# rfLED2.net
KiCad netlist of a schematic drawn in EAGLE
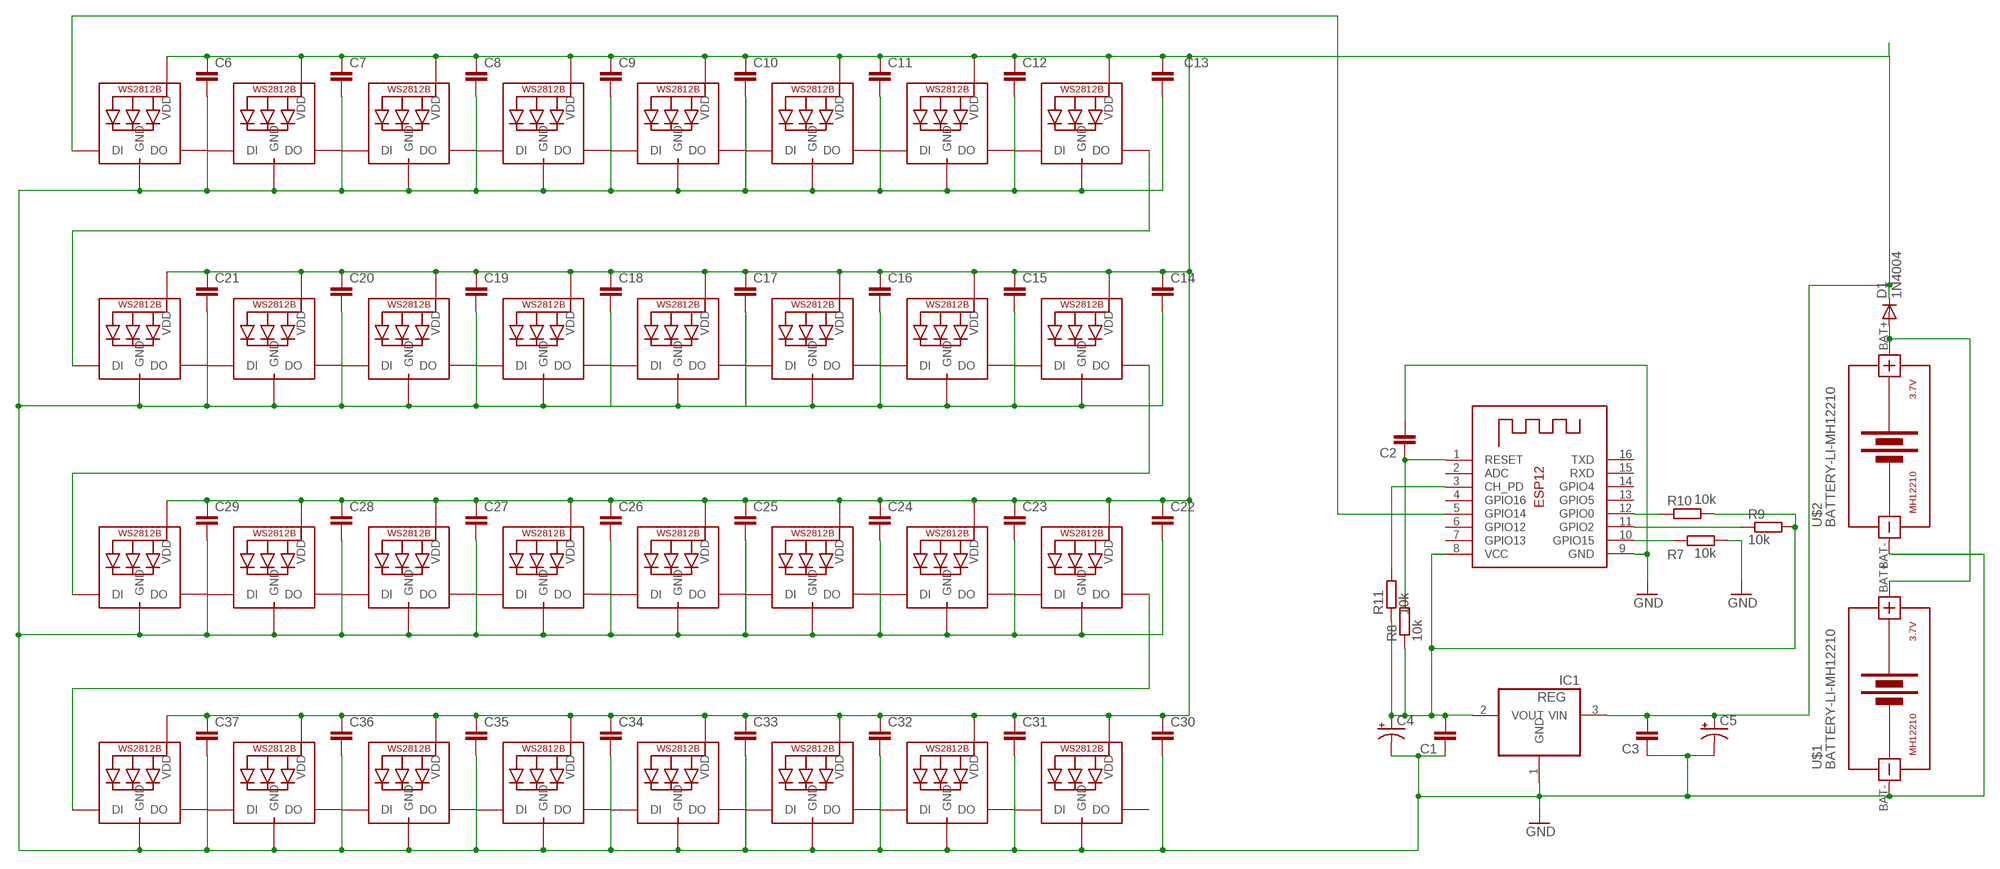
[diagram p0: schematic, sheet 1]

(export (version "E")
  (design (tool "Eeschema 10.0.6"))
  (components
    (comp (ref "C1") (value "C") (footprint "eagle-import:C0805") (libsource (lib "eagle-import") (part "C")))
    (comp (ref "C2") (value "C") (footprint "eagle-import:C0805") (libsource (lib "eagle-import") (part "C")))
    (comp (ref "C3") (value "C") (footprint "eagle-import:C0805") (libsource (lib "eagle-import") (part "C")))
    (comp (ref "C4")
      (value "CPOL-US150CLZ-1010")
      (footprint "eagle-import:150CLZ-1010")
      (libsource (lib "eagle-import") (part "CPOL-US150CLZ-1010"))
    )
    (comp (ref "C5")
      (value "CPOL-US150CLZ-1010")
      (footprint "eagle-import:150CLZ-1010")
      (libsource (lib "eagle-import") (part "CPOL-US150CLZ-1010"))
    )
    (comp (ref "C6") (value "C") (footprint "eagle-import:C0805") (libsource (lib "eagle-import") (part "C")))
    (comp (ref "C7") (value "C") (footprint "eagle-import:C0805") (libsource (lib "eagle-import") (part "C")))
    (comp (ref "C8") (value "C") (footprint "eagle-import:C0805") (libsource (lib "eagle-import") (part "C")))
    (comp (ref "C9") (value "C") (footprint "eagle-import:C0805") (libsource (lib "eagle-import") (part "C")))
    (comp (ref "C10")
      (value "C")
      (footprint "eagle-import:C0805")
      (libsource (lib "eagle-import") (part "C"))
    )
    (comp (ref "C11")
      (value "C")
      (footprint "eagle-import:C0805")
      (libsource (lib "eagle-import") (part "C"))
    )
    (comp (ref "C12")
      (value "C")
      (footprint "eagle-import:C0805")
      (libsource (lib "eagle-import") (part "C"))
    )
    (comp (ref "C13")
      (value "C")
      (footprint "eagle-import:C0805")
      (libsource (lib "eagle-import") (part "C"))
    )
    (comp (ref "C14")
      (value "C")
      (footprint "eagle-import:C0805")
      (libsource (lib "eagle-import") (part "C"))
    )
    (comp (ref "C15")
      (value "C")
      (footprint "eagle-import:C0805")
      (libsource (lib "eagle-import") (part "C"))
    )
    (comp (ref "C16")
      (value "C")
      (footprint "eagle-import:C0805")
      (libsource (lib "eagle-import") (part "C"))
    )
    (comp (ref "C17")
      (value "C")
      (footprint "eagle-import:C0805")
      (libsource (lib "eagle-import") (part "C"))
    )
    (comp (ref "C18")
      (value "C")
      (footprint "eagle-import:C0805")
      (libsource (lib "eagle-import") (part "C"))
    )
    (comp (ref "C19")
      (value "C")
      (footprint "eagle-import:C0805")
      (libsource (lib "eagle-import") (part "C"))
    )
    (comp (ref "C20")
      (value "C")
      (footprint "eagle-import:C0805")
      (libsource (lib "eagle-import") (part "C"))
    )
    (comp (ref "C21")
      (value "C")
      (footprint "eagle-import:C0805")
      (libsource (lib "eagle-import") (part "C"))
    )
    (comp (ref "C22")
      (value "C")
      (footprint "eagle-import:C0805")
      (libsource (lib "eagle-import") (part "C"))
    )
    (comp (ref "C23")
      (value "C")
      (footprint "eagle-import:C0805")
      (libsource (lib "eagle-import") (part "C"))
    )
    (comp (ref "C24")
      (value "C")
      (footprint "eagle-import:C0805")
      (libsource (lib "eagle-import") (part "C"))
    )
    (comp (ref "C25")
      (value "C")
      (footprint "eagle-import:C0805")
      (libsource (lib "eagle-import") (part "C"))
    )
    (comp (ref "C26")
      (value "C")
      (footprint "eagle-import:C0805")
      (libsource (lib "eagle-import") (part "C"))
    )
    (comp (ref "C27")
      (value "C")
      (footprint "eagle-import:C0805")
      (libsource (lib "eagle-import") (part "C"))
    )
    (comp (ref "C28")
      (value "C")
      (footprint "eagle-import:C0805")
      (libsource (lib "eagle-import") (part "C"))
    )
    (comp (ref "C29")
      (value "C")
      (footprint "eagle-import:C0805")
      (libsource (lib "eagle-import") (part "C"))
    )
    (comp (ref "C30")
      (value "C")
      (footprint "eagle-import:C0805")
      (libsource (lib "eagle-import") (part "C"))
    )
    (comp (ref "C31")
      (value "C")
      (footprint "eagle-import:C0805")
      (libsource (lib "eagle-import") (part "C"))
    )
    (comp (ref "C32")
      (value "C")
      (footprint "eagle-import:C0805")
      (libsource (lib "eagle-import") (part "C"))
    )
    (comp (ref "C33")
      (value "C")
      (footprint "eagle-import:C0805")
      (libsource (lib "eagle-import") (part "C"))
    )
    (comp (ref "C34")
      (value "C")
      (footprint "eagle-import:C0805")
      (libsource (lib "eagle-import") (part "C"))
    )
    (comp (ref "C35")
      (value "C")
      (footprint "eagle-import:C0805")
      (libsource (lib "eagle-import") (part "C"))
    )
    (comp (ref "C36")
      (value "C")
      (footprint "eagle-import:C0805")
      (libsource (lib "eagle-import") (part "C"))
    )
    (comp (ref "C37")
      (value "C")
      (footprint "eagle-import:C0805")
      (libsource (lib "eagle-import") (part "C"))
    )
    (comp (ref "D1")
      (value "1N4004")
      (footprint "eagle-import:DO41-10")
      (libsource (lib "eagle-import") (part "1N4004"))
    )
    (comp (ref "IC1")
      (value "REG")
      (footprint "eagle-import:SOT223")
      (fields (field (name "MPN") "REG1117"))
      (libsource (lib "eagle-import") (part "REG1117"))
    )
    (comp (ref "LED1")
      (value "WS2812B5050")
      (footprint "eagle-import:WS2812B")
      (libsource (lib "eagle-import") (part "WS2812B5050"))
    )
    (comp (ref "LED2")
      (value "WS2812B5050")
      (footprint "eagle-import:WS2812B")
      (libsource (lib "eagle-import") (part "WS2812B5050"))
    )
    (comp (ref "LED3")
      (value "WS2812B5050")
      (footprint "eagle-import:WS2812B")
      (libsource (lib "eagle-import") (part "WS2812B5050"))
    )
    (comp (ref "LED4")
      (value "WS2812B5050")
      (footprint "eagle-import:WS2812B")
      (libsource (lib "eagle-import") (part "WS2812B5050"))
    )
    (comp (ref "LED5")
      (value "WS2812B5050")
      (footprint "eagle-import:WS2812B")
      (libsource (lib "eagle-import") (part "WS2812B5050"))
    )
    (comp (ref "LED6")
      (value "WS2812B5050")
      (footprint "eagle-import:WS2812B")
      (libsource (lib "eagle-import") (part "WS2812B5050"))
    )
    (comp (ref "LED7")
      (value "WS2812B5050")
      (footprint "eagle-import:WS2812B")
      (libsource (lib "eagle-import") (part "WS2812B5050"))
    )
    (comp (ref "LED8")
      (value "WS2812B5050")
      (footprint "eagle-import:WS2812B")
      (libsource (lib "eagle-import") (part "WS2812B5050"))
    )
    (comp (ref "LED9")
      (value "WS2812B5050")
      (footprint "eagle-import:WS2812B")
      (libsource (lib "eagle-import") (part "WS2812B5050"))
    )
    (comp (ref "LED10")
      (value "WS2812B5050")
      (footprint "eagle-import:WS2812B")
      (libsource (lib "eagle-import") (part "WS2812B5050"))
    )
    (comp (ref "LED11")
      (value "WS2812B5050")
      (footprint "eagle-import:WS2812B")
      (libsource (lib "eagle-import") (part "WS2812B5050"))
    )
    (comp (ref "LED12")
      (value "WS2812B5050")
      (footprint "eagle-import:WS2812B")
      (libsource (lib "eagle-import") (part "WS2812B5050"))
    )
    (comp (ref "LED13")
      (value "WS2812B5050")
      (footprint "eagle-import:WS2812B")
      (libsource (lib "eagle-import") (part "WS2812B5050"))
    )
    (comp (ref "LED14")
      (value "WS2812B5050")
      (footprint "eagle-import:WS2812B")
      (libsource (lib "eagle-import") (part "WS2812B5050"))
    )
    (comp (ref "LED15")
      (value "WS2812B5050")
      (footprint "eagle-import:WS2812B")
      (libsource (lib "eagle-import") (part "WS2812B5050"))
    )
    (comp (ref "LED16")
      (value "WS2812B5050")
      (footprint "eagle-import:WS2812B")
      (libsource (lib "eagle-import") (part "WS2812B5050"))
    )
    (comp (ref "LED17")
      (value "WS2812B5050")
      (footprint "eagle-import:WS2812B")
      (libsource (lib "eagle-import") (part "WS2812B5050"))
    )
    (comp (ref "LED18")
      (value "WS2812B5050")
      (footprint "eagle-import:WS2812B")
      (libsource (lib "eagle-import") (part "WS2812B5050"))
    )
    (comp (ref "LED19")
      (value "WS2812B5050")
      (footprint "eagle-import:WS2812B")
      (libsource (lib "eagle-import") (part "WS2812B5050"))
    )
    (comp (ref "LED20")
      (value "WS2812B5050")
      (footprint "eagle-import:WS2812B")
      (libsource (lib "eagle-import") (part "WS2812B5050"))
    )
    (comp (ref "LED21")
      (value "WS2812B5050")
      (footprint "eagle-import:WS2812B")
      (libsource (lib "eagle-import") (part "WS2812B5050"))
    )
    (comp (ref "LED22")
      (value "WS2812B5050")
      (footprint "eagle-import:WS2812B")
      (libsource (lib "eagle-import") (part "WS2812B5050"))
    )
    (comp (ref "LED23")
      (value "WS2812B5050")
      (footprint "eagle-import:WS2812B")
      (libsource (lib "eagle-import") (part "WS2812B5050"))
    )
    (comp (ref "LED24")
      (value "WS2812B5050")
      (footprint "eagle-import:WS2812B")
      (libsource (lib "eagle-import") (part "WS2812B5050"))
    )
    (comp (ref "LED25")
      (value "WS2812B5050")
      (footprint "eagle-import:WS2812B")
      (libsource (lib "eagle-import") (part "WS2812B5050"))
    )
    (comp (ref "LED26")
      (value "WS2812B5050")
      (footprint "eagle-import:WS2812B")
      (libsource (lib "eagle-import") (part "WS2812B5050"))
    )
    (comp (ref "LED27")
      (value "WS2812B5050")
      (footprint "eagle-import:WS2812B")
      (libsource (lib "eagle-import") (part "WS2812B5050"))
    )
    (comp (ref "LED28")
      (value "WS2812B5050")
      (footprint "eagle-import:WS2812B")
      (libsource (lib "eagle-import") (part "WS2812B5050"))
    )
    (comp (ref "LED29")
      (value "WS2812B5050")
      (footprint "eagle-import:WS2812B")
      (libsource (lib "eagle-import") (part "WS2812B5050"))
    )
    (comp (ref "LED30")
      (value "WS2812B5050")
      (footprint "eagle-import:WS2812B")
      (libsource (lib "eagle-import") (part "WS2812B5050"))
    )
    (comp (ref "LED31")
      (value "WS2812B5050")
      (footprint "eagle-import:WS2812B")
      (libsource (lib "eagle-import") (part "WS2812B5050"))
    )
    (comp (ref "LED32")
      (value "WS2812B5050")
      (footprint "eagle-import:WS2812B")
      (libsource (lib "eagle-import") (part "WS2812B5050"))
    )
    (comp (ref "R7")
      (value "10k")
      (footprint "eagle-import:R1206")
      (libsource (lib "eagle-import") (part "RR1206"))
    )
    (comp (ref "R8")
      (value "10k")
      (footprint "eagle-import:R1206")
      (libsource (lib "eagle-import") (part "RR1206"))
    )
    (comp (ref "R9")
      (value "10k")
      (footprint "eagle-import:R1206")
      (libsource (lib "eagle-import") (part "RR1206"))
    )
    (comp (ref "R10")
      (value "10k")
      (footprint "eagle-import:R1206")
      (libsource (lib "eagle-import") (part "RR1206"))
    )
    (comp (ref "R11")
      (value "10k")
      (footprint "eagle-import:R1206")
      (libsource (lib "eagle-import") (part "RR1206"))
    )
    (comp (ref "U$1")
      (value "BATTERY-LI-MH12210")
      (footprint "eagle-import:BATTERY-LI-MH12210")
      (libsource (lib "eagle-import") (part "BATTERY-LI-MH12210"))
    )
    (comp (ref "U$2")
      (value "BATTERY-LI-MH12210")
      (footprint "eagle-import:BATTERY-LI-MH12210")
      (libsource (lib "eagle-import") (part "BATTERY-LI-MH12210"))
    )
    (comp (ref "X1")
      (value "ESP-12")
      (footprint "eagle-import:ESP-12")
      (libsource (lib "eagle-import") (part "ESP-12"))
    )
  )
  (nets
    (net (code "1") (name "GND") (class "Default")
      (node (ref "C1") (pin "1") (pinfunction "1_1") (pintype "passive"))
      (node (ref "C10") (pin "2") (pinfunction "2_2") (pintype "passive"))
      (node (ref "C11") (pin "2") (pinfunction "2_2") (pintype "passive"))
      (node (ref "C12") (pin "2") (pinfunction "2_2") (pintype "passive"))
      (node (ref "C13") (pin "2") (pinfunction "2_2") (pintype "passive"))
      (node (ref "C14") (pin "2") (pinfunction "2_2") (pintype "passive"))
      (node (ref "C15") (pin "2") (pinfunction "2_2") (pintype "passive"))
      (node (ref "C16") (pin "2") (pinfunction "2_2") (pintype "passive"))
      (node (ref "C17") (pin "2") (pinfunction "2_2") (pintype "passive"))
      (node (ref "C18") (pin "2") (pinfunction "2_2") (pintype "passive"))
      (node (ref "C19") (pin "2") (pinfunction "2_2") (pintype "passive"))
      (node (ref "C2") (pin "2") (pinfunction "2_2") (pintype "passive"))
      (node (ref "C20") (pin "2") (pinfunction "2_2") (pintype "passive"))
      (node (ref "C21") (pin "2") (pinfunction "2_2") (pintype "passive"))
      (node (ref "C22") (pin "2") (pinfunction "2_2") (pintype "passive"))
      (node (ref "C23") (pin "2") (pinfunction "2_2") (pintype "passive"))
      (node (ref "C24") (pin "2") (pinfunction "2_2") (pintype "passive"))
      (node (ref "C25") (pin "2") (pinfunction "2_2") (pintype "passive"))
      (node (ref "C26") (pin "2") (pinfunction "2_2") (pintype "passive"))
      (node (ref "C27") (pin "2") (pinfunction "2_2") (pintype "passive"))
      (node (ref "C28") (pin "2") (pinfunction "2_2") (pintype "passive"))
      (node (ref "C29") (pin "2") (pinfunction "2_2") (pintype "passive"))
      (node (ref "C3") (pin "1") (pinfunction "1_1") (pintype "passive"))
      (node (ref "C30") (pin "2") (pinfunction "2_2") (pintype "passive"))
      (node (ref "C31") (pin "2") (pinfunction "2_2") (pintype "passive"))
      (node (ref "C32") (pin "2") (pinfunction "2_2") (pintype "passive"))
      (node (ref "C33") (pin "2") (pinfunction "2_2") (pintype "passive"))
      (node (ref "C34") (pin "2") (pinfunction "2_2") (pintype "passive"))
      (node (ref "C35") (pin "2") (pinfunction "2_2") (pintype "passive"))
      (node (ref "C36") (pin "2") (pinfunction "2_2") (pintype "passive"))
      (node (ref "C37") (pin "2") (pinfunction "2_2") (pintype "passive"))
      (node (ref "C4") (pin "-") (pinfunction "-_-") (pintype "passive"))
      (node (ref "C5") (pin "-") (pinfunction "-_-") (pintype "passive"))
      (node (ref "C6") (pin "2") (pinfunction "2_2") (pintype "passive"))
      (node (ref "C7") (pin "2") (pinfunction "2_2") (pintype "passive"))
      (node (ref "C8") (pin "2") (pinfunction "2_2") (pintype "passive"))
      (node (ref "C9") (pin "2") (pinfunction "2_2") (pintype "passive"))
      (node (ref "IC1") (pin "1") (pinfunction "GND_1") (pintype "power_in"))
      (node (ref "LED1") (pin "3-GND") (pinfunction "GND_3-GND") (pintype "power_in"))
      (node (ref "LED10") (pin "3-GND") (pinfunction "GND_3-GND") (pintype "power_in"))
      (node (ref "LED11") (pin "3-GND") (pinfunction "GND_3-GND") (pintype "power_in"))
      (node (ref "LED12") (pin "3-GND") (pinfunction "GND_3-GND") (pintype "power_in"))
      (node (ref "LED13") (pin "3-GND") (pinfunction "GND_3-GND") (pintype "power_in"))
      (node (ref "LED14") (pin "3-GND") (pinfunction "GND_3-GND") (pintype "power_in"))
      (node (ref "LED15") (pin "3-GND") (pinfunction "GND_3-GND") (pintype "power_in"))
      (node (ref "LED16") (pin "3-GND") (pinfunction "GND_3-GND") (pintype "power_in"))
      (node (ref "LED17") (pin "3-GND") (pinfunction "GND_3-GND") (pintype "power_in"))
      (node (ref "LED18") (pin "3-GND") (pinfunction "GND_3-GND") (pintype "power_in"))
      (node (ref "LED19") (pin "3-GND") (pinfunction "GND_3-GND") (pintype "power_in"))
      (node (ref "LED2") (pin "3-GND") (pinfunction "GND_3-GND") (pintype "power_in"))
      (node (ref "LED20") (pin "3-GND") (pinfunction "GND_3-GND") (pintype "power_in"))
      (node (ref "LED21") (pin "3-GND") (pinfunction "GND_3-GND") (pintype "power_in"))
      (node (ref "LED22") (pin "3-GND") (pinfunction "GND_3-GND") (pintype "power_in"))
      (node (ref "LED23") (pin "3-GND") (pinfunction "GND_3-GND") (pintype "power_in"))
      (node (ref "LED24") (pin "3-GND") (pinfunction "GND_3-GND") (pintype "power_in"))
      (node (ref "LED25") (pin "3-GND") (pinfunction "GND_3-GND") (pintype "power_in"))
      (node (ref "LED26") (pin "3-GND") (pinfunction "GND_3-GND") (pintype "power_in"))
      (node (ref "LED27") (pin "3-GND") (pinfunction "GND_3-GND") (pintype "power_in"))
      (node (ref "LED28") (pin "3-GND") (pinfunction "GND_3-GND") (pintype "power_in"))
      (node (ref "LED29") (pin "3-GND") (pinfunction "GND_3-GND") (pintype "power_in"))
      (node (ref "LED3") (pin "3-GND") (pinfunction "GND_3-GND") (pintype "power_in"))
      (node (ref "LED30") (pin "3-GND") (pinfunction "GND_3-GND") (pintype "power_in"))
      (node (ref "LED31") (pin "3-GND") (pinfunction "GND_3-GND") (pintype "power_in"))
      (node (ref "LED32") (pin "3-GND") (pinfunction "GND_3-GND") (pintype "power_in"))
      (node (ref "LED4") (pin "3-GND") (pinfunction "GND_3-GND") (pintype "power_in"))
      (node (ref "LED5") (pin "3-GND") (pinfunction "GND_3-GND") (pintype "power_in"))
      (node (ref "LED6") (pin "3-GND") (pinfunction "GND_3-GND") (pintype "power_in"))
      (node (ref "LED7") (pin "3-GND") (pinfunction "GND_3-GND") (pintype "power_in"))
      (node (ref "LED8") (pin "3-GND") (pinfunction "GND_3-GND") (pintype "power_in"))
      (node (ref "LED9") (pin "3-GND") (pinfunction "GND_3-GND") (pintype "power_in"))
      (node (ref "R7") (pin "2") (pinfunction "2_2") (pintype "passive"))
      (node (ref "U$1") (pin "BAT-") (pinfunction "BAT-_BAT-") (pintype "power_in"))
      (node (ref "U$2") (pin "BAT-") (pinfunction "BAT-_BAT-") (pintype "power_in"))
      (node (ref "X1") (pin "9") (pinfunction "GND_9") (pintype "power_in"))
    )
    (net (code "2") (name "Net-(D1-PadA)") (class "Default")
      (node (ref "D1") (pin "A") (pinfunction "A_A") (pintype "passive"))
      (node (ref "U$1") (pin "BAT+") (pinfunction "BAT+_BAT+") (pintype "power_in"))
      (node (ref "U$2") (pin "BAT+") (pinfunction "BAT+_BAT+") (pintype "power_in"))
    )
    (net (code "3") (name "Net-(IC1-VIN)") (class "Default")
      (node (ref "C10") (pin "1") (pinfunction "1_1") (pintype "passive"))
      (node (ref "C11") (pin "1") (pinfunction "1_1") (pintype "passive"))
      (node (ref "C12") (pin "1") (pinfunction "1_1") (pintype "passive"))
      (node (ref "C13") (pin "1") (pinfunction "1_1") (pintype "passive"))
      (node (ref "C14") (pin "1") (pinfunction "1_1") (pintype "passive"))
      (node (ref "C15") (pin "1") (pinfunction "1_1") (pintype "passive"))
      (node (ref "C16") (pin "1") (pinfunction "1_1") (pintype "passive"))
      (node (ref "C17") (pin "1") (pinfunction "1_1") (pintype "passive"))
      (node (ref "C18") (pin "1") (pinfunction "1_1") (pintype "passive"))
      (node (ref "C19") (pin "1") (pinfunction "1_1") (pintype "passive"))
      (node (ref "C20") (pin "1") (pinfunction "1_1") (pintype "passive"))
      (node (ref "C21") (pin "1") (pinfunction "1_1") (pintype "passive"))
      (node (ref "C22") (pin "1") (pinfunction "1_1") (pintype "passive"))
      (node (ref "C23") (pin "1") (pinfunction "1_1") (pintype "passive"))
      (node (ref "C24") (pin "1") (pinfunction "1_1") (pintype "passive"))
      (node (ref "C25") (pin "1") (pinfunction "1_1") (pintype "passive"))
      (node (ref "C26") (pin "1") (pinfunction "1_1") (pintype "passive"))
      (node (ref "C27") (pin "1") (pinfunction "1_1") (pintype "passive"))
      (node (ref "C28") (pin "1") (pinfunction "1_1") (pintype "passive"))
      (node (ref "C29") (pin "1") (pinfunction "1_1") (pintype "passive"))
      (node (ref "C3") (pin "2") (pinfunction "2_2") (pintype "passive"))
      (node (ref "C30") (pin "1") (pinfunction "1_1") (pintype "passive"))
      (node (ref "C31") (pin "1") (pinfunction "1_1") (pintype "passive"))
      (node (ref "C32") (pin "1") (pinfunction "1_1") (pintype "passive"))
      (node (ref "C33") (pin "1") (pinfunction "1_1") (pintype "passive"))
      (node (ref "C34") (pin "1") (pinfunction "1_1") (pintype "passive"))
      (node (ref "C35") (pin "1") (pinfunction "1_1") (pintype "passive"))
      (node (ref "C36") (pin "1") (pinfunction "1_1") (pintype "passive"))
      (node (ref "C37") (pin "1") (pinfunction "1_1") (pintype "passive"))
      (node (ref "C5") (pin "+") (pinfunction "+_+") (pintype "passive"))
      (node (ref "C6") (pin "1") (pinfunction "1_1") (pintype "passive"))
      (node (ref "C7") (pin "1") (pinfunction "1_1") (pintype "passive"))
      (node (ref "C8") (pin "1") (pinfunction "1_1") (pintype "passive"))
      (node (ref "C9") (pin "1") (pinfunction "1_1") (pintype "passive"))
      (node (ref "D1") (pin "C") (pinfunction "C_C") (pintype "passive"))
      (node (ref "IC1") (pin "3") (pinfunction "VIN_3") (pintype "input"))
      (node (ref "LED1") (pin "1-VDD") (pinfunction "VDD_1-VDD") (pintype "power_in"))
      (node (ref "LED10") (pin "1-VDD") (pinfunction "VDD_1-VDD") (pintype "power_in"))
      (node (ref "LED11") (pin "1-VDD") (pinfunction "VDD_1-VDD") (pintype "power_in"))
      (node (ref "LED12") (pin "1-VDD") (pinfunction "VDD_1-VDD") (pintype "power_in"))
      (node (ref "LED13") (pin "1-VDD") (pinfunction "VDD_1-VDD") (pintype "power_in"))
      (node (ref "LED14") (pin "1-VDD") (pinfunction "VDD_1-VDD") (pintype "power_in"))
      (node (ref "LED15") (pin "1-VDD") (pinfunction "VDD_1-VDD") (pintype "power_in"))
      (node (ref "LED16") (pin "1-VDD") (pinfunction "VDD_1-VDD") (pintype "power_in"))
      (node (ref "LED17") (pin "1-VDD") (pinfunction "VDD_1-VDD") (pintype "power_in"))
      (node (ref "LED18") (pin "1-VDD") (pinfunction "VDD_1-VDD") (pintype "power_in"))
      (node (ref "LED19") (pin "1-VDD") (pinfunction "VDD_1-VDD") (pintype "power_in"))
      (node (ref "LED2") (pin "1-VDD") (pinfunction "VDD_1-VDD") (pintype "power_in"))
      (node (ref "LED20") (pin "1-VDD") (pinfunction "VDD_1-VDD") (pintype "power_in"))
      (node (ref "LED21") (pin "1-VDD") (pinfunction "VDD_1-VDD") (pintype "power_in"))
      (node (ref "LED22") (pin "1-VDD") (pinfunction "VDD_1-VDD") (pintype "power_in"))
      (node (ref "LED23") (pin "1-VDD") (pinfunction "VDD_1-VDD") (pintype "power_in"))
      (node (ref "LED24") (pin "1-VDD") (pinfunction "VDD_1-VDD") (pintype "power_in"))
      (node (ref "LED25") (pin "1-VDD") (pinfunction "VDD_1-VDD") (pintype "power_in"))
      (node (ref "LED26") (pin "1-VDD") (pinfunction "VDD_1-VDD") (pintype "power_in"))
      (node (ref "LED27") (pin "1-VDD") (pinfunction "VDD_1-VDD") (pintype "power_in"))
      (node (ref "LED28") (pin "1-VDD") (pinfunction "VDD_1-VDD") (pintype "power_in"))
      (node (ref "LED29") (pin "1-VDD") (pinfunction "VDD_1-VDD") (pintype "power_in"))
      (node (ref "LED3") (pin "1-VDD") (pinfunction "VDD_1-VDD") (pintype "power_in"))
      (node (ref "LED30") (pin "1-VDD") (pinfunction "VDD_1-VDD") (pintype "power_in"))
      (node (ref "LED31") (pin "1-VDD") (pinfunction "VDD_1-VDD") (pintype "power_in"))
      (node (ref "LED32") (pin "1-VDD") (pinfunction "VDD_1-VDD") (pintype "power_in"))
      (node (ref "LED4") (pin "1-VDD") (pinfunction "VDD_1-VDD") (pintype "power_in"))
      (node (ref "LED5") (pin "1-VDD") (pinfunction "VDD_1-VDD") (pintype "power_in"))
      (node (ref "LED6") (pin "1-VDD") (pinfunction "VDD_1-VDD") (pintype "power_in"))
      (node (ref "LED7") (pin "1-VDD") (pinfunction "VDD_1-VDD") (pintype "power_in"))
      (node (ref "LED8") (pin "1-VDD") (pinfunction "VDD_1-VDD") (pintype "power_in"))
      (node (ref "LED9") (pin "1-VDD") (pinfunction "VDD_1-VDD") (pintype "power_in"))
    )
    (net (code "4") (name "Net-(IC1-VOUT)") (class "Default")
      (node (ref "C1") (pin "2") (pinfunction "2_2") (pintype "passive"))
      (node (ref "C4") (pin "+") (pinfunction "+_+") (pintype "passive"))
      (node (ref "IC1") (pin "2") (pinfunction "VOUT_2") (pintype "output"))
      (node (ref "R10") (pin "2") (pinfunction "2_2") (pintype "passive"))
      (node (ref "R11") (pin "1") (pinfunction "1_1") (pintype "passive"))
      (node (ref "R8") (pin "1") (pinfunction "1_1") (pintype "passive"))
      (node (ref "R9") (pin "2") (pinfunction "2_2") (pintype "passive"))
      (node (ref "X1") (pin "8") (pinfunction "VCC_8") (pintype "power_in"))
    )
    (net (code "5") (name "Net-(LED1-DI)") (class "Default")
      (node (ref "LED1") (pin "4-DIN") (pinfunction "DI_4-DIN") (pintype "input"))
      (node (ref "X1") (pin "5") (pinfunction "GPIO14_5") (pintype "bidirectional"))
    )
    (net (code "6") (name "Net-(LED1-DO)") (class "Default")
      (node (ref "LED1") (pin "2-DOUT") (pinfunction "DO_2-DOUT") (pintype "output"))
      (node (ref "LED2") (pin "4-DIN") (pinfunction "DI_4-DIN") (pintype "input"))
    )
    (net (code "7") (name "Net-(LED2-DO)") (class "Default")
      (node (ref "LED2") (pin "2-DOUT") (pinfunction "DO_2-DOUT") (pintype "output"))
      (node (ref "LED3") (pin "4-DIN") (pinfunction "DI_4-DIN") (pintype "input"))
    )
    (net (code "8") (name "Net-(LED3-DO)") (class "Default")
      (node (ref "LED3") (pin "2-DOUT") (pinfunction "DO_2-DOUT") (pintype "output"))
      (node (ref "LED4") (pin "4-DIN") (pinfunction "DI_4-DIN") (pintype "input"))
    )
    (net (code "9") (name "Net-(LED4-DO)") (class "Default")
      (node (ref "LED4") (pin "2-DOUT") (pinfunction "DO_2-DOUT") (pintype "output"))
      (node (ref "LED5") (pin "4-DIN") (pinfunction "DI_4-DIN") (pintype "input"))
    )
    (net (code "10") (name "Net-(LED5-DO)") (class "Default")
      (node (ref "LED5") (pin "2-DOUT") (pinfunction "DO_2-DOUT") (pintype "output"))
      (node (ref "LED6") (pin "4-DIN") (pinfunction "DI_4-DIN") (pintype "input"))
    )
    (net (code "11") (name "Net-(LED6-DO)") (class "Default")
      (node (ref "LED6") (pin "2-DOUT") (pinfunction "DO_2-DOUT") (pintype "output"))
      (node (ref "LED7") (pin "4-DIN") (pinfunction "DI_4-DIN") (pintype "input"))
    )
    (net (code "12") (name "Net-(LED7-DO)") (class "Default")
      (node (ref "LED7") (pin "2-DOUT") (pinfunction "DO_2-DOUT") (pintype "output"))
      (node (ref "LED8") (pin "4-DIN") (pinfunction "DI_4-DIN") (pintype "input"))
    )
    (net (code "13") (name "Net-(LED8-DO)") (class "Default")
      (node (ref "LED8") (pin "2-DOUT") (pinfunction "DO_2-DOUT") (pintype "output"))
      (node (ref "LED9") (pin "4-DIN") (pinfunction "DI_4-DIN") (pintype "input"))
    )
    (net (code "14") (name "Net-(LED10-DI)") (class "Default")
      (node (ref "LED10") (pin "4-DIN") (pinfunction "DI_4-DIN") (pintype "input"))
      (node (ref "LED9") (pin "2-DOUT") (pinfunction "DO_2-DOUT") (pintype "output"))
    )
    (net (code "15") (name "Net-(LED10-DO)") (class "Default")
      (node (ref "LED10") (pin "2-DOUT") (pinfunction "DO_2-DOUT") (pintype "output"))
      (node (ref "LED11") (pin "4-DIN") (pinfunction "DI_4-DIN") (pintype "input"))
    )
    (net (code "16") (name "Net-(LED11-DO)") (class "Default")
      (node (ref "LED11") (pin "2-DOUT") (pinfunction "DO_2-DOUT") (pintype "output"))
      (node (ref "LED12") (pin "4-DIN") (pinfunction "DI_4-DIN") (pintype "input"))
    )
    (net (code "17") (name "Net-(LED12-DO)") (class "Default")
      (node (ref "LED12") (pin "2-DOUT") (pinfunction "DO_2-DOUT") (pintype "output"))
      (node (ref "LED13") (pin "4-DIN") (pinfunction "DI_4-DIN") (pintype "input"))
    )
    (net (code "18") (name "Net-(LED13-DO)") (class "Default")
      (node (ref "LED13") (pin "2-DOUT") (pinfunction "DO_2-DOUT") (pintype "output"))
      (node (ref "LED14") (pin "4-DIN") (pinfunction "DI_4-DIN") (pintype "input"))
    )
    (net (code "19") (name "Net-(LED14-DO)") (class "Default")
      (node (ref "LED14") (pin "2-DOUT") (pinfunction "DO_2-DOUT") (pintype "output"))
      (node (ref "LED15") (pin "4-DIN") (pinfunction "DI_4-DIN") (pintype "input"))
    )
    (net (code "20") (name "Net-(LED15-DO)") (class "Default")
      (node (ref "LED15") (pin "2-DOUT") (pinfunction "DO_2-DOUT") (pintype "output"))
      (node (ref "LED16") (pin "4-DIN") (pinfunction "DI_4-DIN") (pintype "input"))
    )
    (net (code "21") (name "Net-(LED16-DO)") (class "Default")
      (node (ref "LED16") (pin "2-DOUT") (pinfunction "DO_2-DOUT") (pintype "output"))
      (node (ref "LED17") (pin "4-DIN") (pinfunction "DI_4-DIN") (pintype "input"))
    )
    (net (code "22") (name "Net-(LED17-DO)") (class "Default")
      (node (ref "LED17") (pin "2-DOUT") (pinfunction "DO_2-DOUT") (pintype "output"))
      (node (ref "LED18") (pin "4-DIN") (pinfunction "DI_4-DIN") (pintype "input"))
    )
    (net (code "23") (name "Net-(LED18-DO)") (class "Default")
      (node (ref "LED18") (pin "2-DOUT") (pinfunction "DO_2-DOUT") (pintype "output"))
      (node (ref "LED19") (pin "4-DIN") (pinfunction "DI_4-DIN") (pintype "input"))
    )
    (net (code "24") (name "Net-(LED19-DO)") (class "Default")
      (node (ref "LED19") (pin "2-DOUT") (pinfunction "DO_2-DOUT") (pintype "output"))
      (node (ref "LED20") (pin "4-DIN") (pinfunction "DI_4-DIN") (pintype "input"))
    )
    (net (code "25") (name "Net-(LED20-DO)") (class "Default")
      (node (ref "LED20") (pin "2-DOUT") (pinfunction "DO_2-DOUT") (pintype "output"))
      (node (ref "LED21") (pin "4-DIN") (pinfunction "DI_4-DIN") (pintype "input"))
    )
    (net (code "26") (name "Net-(LED21-DO)") (class "Default")
      (node (ref "LED21") (pin "2-DOUT") (pinfunction "DO_2-DOUT") (pintype "output"))
      (node (ref "LED22") (pin "4-DIN") (pinfunction "DI_4-DIN") (pintype "input"))
    )
    (net (code "27") (name "Net-(LED22-DO)") (class "Default")
      (node (ref "LED22") (pin "2-DOUT") (pinfunction "DO_2-DOUT") (pintype "output"))
      (node (ref "LED23") (pin "4-DIN") (pinfunction "DI_4-DIN") (pintype "input"))
    )
    (net (code "28") (name "Net-(LED23-DO)") (class "Default")
      (node (ref "LED23") (pin "2-DOUT") (pinfunction "DO_2-DOUT") (pintype "output"))
      (node (ref "LED24") (pin "4-DIN") (pinfunction "DI_4-DIN") (pintype "input"))
    )
    (net (code "29") (name "Net-(LED24-DO)") (class "Default")
      (node (ref "LED24") (pin "2-DOUT") (pinfunction "DO_2-DOUT") (pintype "output"))
      (node (ref "LED25") (pin "4-DIN") (pinfunction "DI_4-DIN") (pintype "input"))
    )
    (net (code "30") (name "Net-(LED25-DO)") (class "Default")
      (node (ref "LED25") (pin "2-DOUT") (pinfunction "DO_2-DOUT") (pintype "output"))
      (node (ref "LED26") (pin "4-DIN") (pinfunction "DI_4-DIN") (pintype "input"))
    )
    (net (code "31") (name "Net-(LED26-DO)") (class "Default")
      (node (ref "LED26") (pin "2-DOUT") (pinfunction "DO_2-DOUT") (pintype "output"))
      (node (ref "LED27") (pin "4-DIN") (pinfunction "DI_4-DIN") (pintype "input"))
    )
    (net (code "32") (name "Net-(LED27-DO)") (class "Default")
      (node (ref "LED27") (pin "2-DOUT") (pinfunction "DO_2-DOUT") (pintype "output"))
      (node (ref "LED28") (pin "4-DIN") (pinfunction "DI_4-DIN") (pintype "input"))
    )
    (net (code "33") (name "Net-(LED28-DO)") (class "Default")
      (node (ref "LED28") (pin "2-DOUT") (pinfunction "DO_2-DOUT") (pintype "output"))
      (node (ref "LED29") (pin "4-DIN") (pinfunction "DI_4-DIN") (pintype "input"))
    )
    (net (code "34") (name "Net-(LED29-DO)") (class "Default")
      (node (ref "LED29") (pin "2-DOUT") (pinfunction "DO_2-DOUT") (pintype "output"))
      (node (ref "LED30") (pin "4-DIN") (pinfunction "DI_4-DIN") (pintype "input"))
    )
    (net (code "35") (name "Net-(LED30-DO)") (class "Default")
      (node (ref "LED30") (pin "2-DOUT") (pinfunction "DO_2-DOUT") (pintype "output"))
      (node (ref "LED31") (pin "4-DIN") (pinfunction "DI_4-DIN") (pintype "input"))
    )
    (net (code "36") (name "Net-(LED31-DO)") (class "Default")
      (node (ref "LED31") (pin "2-DOUT") (pinfunction "DO_2-DOUT") (pintype "output"))
      (node (ref "LED32") (pin "4-DIN") (pinfunction "DI_4-DIN") (pintype "input"))
    )
    (net (code "37") (name "Net-(X1-CH_PD)") (class "Default")
      (node (ref "R11") (pin "2") (pinfunction "2_2") (pintype "passive"))
      (node (ref "X1") (pin "3") (pinfunction "CH_PD_3") (pintype "input"))
    )
    (net (code "38") (name "Net-(X1-GPIO0)") (class "Default")
      (node (ref "R10") (pin "1") (pinfunction "1_1") (pintype "passive"))
      (node (ref "X1") (pin "12") (pinfunction "GPIO0_12") (pintype "bidirectional"))
    )
    (net (code "39") (name "Net-(X1-GPIO2)") (class "Default")
      (node (ref "R9") (pin "1") (pinfunction "1_1") (pintype "passive"))
      (node (ref "X1") (pin "11") (pinfunction "GPIO2_11") (pintype "bidirectional"))
    )
    (net (code "40") (name "Net-(X1-GPIO15)") (class "Default")
      (node (ref "R7") (pin "1") (pinfunction "1_1") (pintype "passive"))
      (node (ref "X1") (pin "10") (pinfunction "GPIO15_10") (pintype "bidirectional"))
    )
    (net (code "41") (name "Net-(X1-RESET)") (class "Default")
      (node (ref "C2") (pin "1") (pinfunction "1_1") (pintype "passive"))
      (node (ref "R8") (pin "2") (pinfunction "2_2") (pintype "passive"))
      (node (ref "X1") (pin "1") (pinfunction "RESET_1") (pintype "input"))
    )
    (net (code "42") (name "unconnected-(LED32-DO-Pad2-DOUT)") (class "Default")
      (node (ref "LED32") (pin "2-DOUT") (pinfunction "DO_2-DOUT") (pintype "output"))
    )
    (net (code "43") (name "unconnected-(X1-ADC-Pad2)") (class "Default")
      (node (ref "X1") (pin "2") (pinfunction "ADC_2") (pintype "passive"))
    )
    (net (code "44") (name "unconnected-(X1-GPIO4-Pad14)") (class "Default")
      (node (ref "X1") (pin "14") (pinfunction "GPIO4_14") (pintype "bidirectional"))
    )
    (net (code "45") (name "unconnected-(X1-GPIO5-Pad13)") (class "Default")
      (node (ref "X1") (pin "13") (pinfunction "GPIO5_13") (pintype "bidirectional"))
    )
    (net (code "46") (name "unconnected-(X1-GPIO12-Pad6)") (class "Default")
      (node (ref "X1") (pin "6") (pinfunction "GPIO12_6") (pintype "bidirectional"))
    )
    (net (code "47") (name "unconnected-(X1-GPIO13-Pad7)") (class "Default")
      (node (ref "X1") (pin "7") (pinfunction "GPIO13_7") (pintype "bidirectional"))
    )
    (net (code "48") (name "unconnected-(X1-GPIO16-Pad4)") (class "Default")
      (node (ref "X1") (pin "4") (pinfunction "GPIO16_4") (pintype "bidirectional"))
    )
    (net (code "49") (name "unconnected-(X1-RXD-Pad15)") (class "Default")
      (node (ref "X1") (pin "15") (pinfunction "RXD_15") (pintype "input"))
    )
    (net (code "50") (name "unconnected-(X1-TXD-Pad16)") (class "Default")
      (node (ref "X1") (pin "16") (pinfunction "TXD_16") (pintype "output"))
    )
  )
)
